# MosfetV4.net
KiCad netlist of a schematic drawn in EAGLE
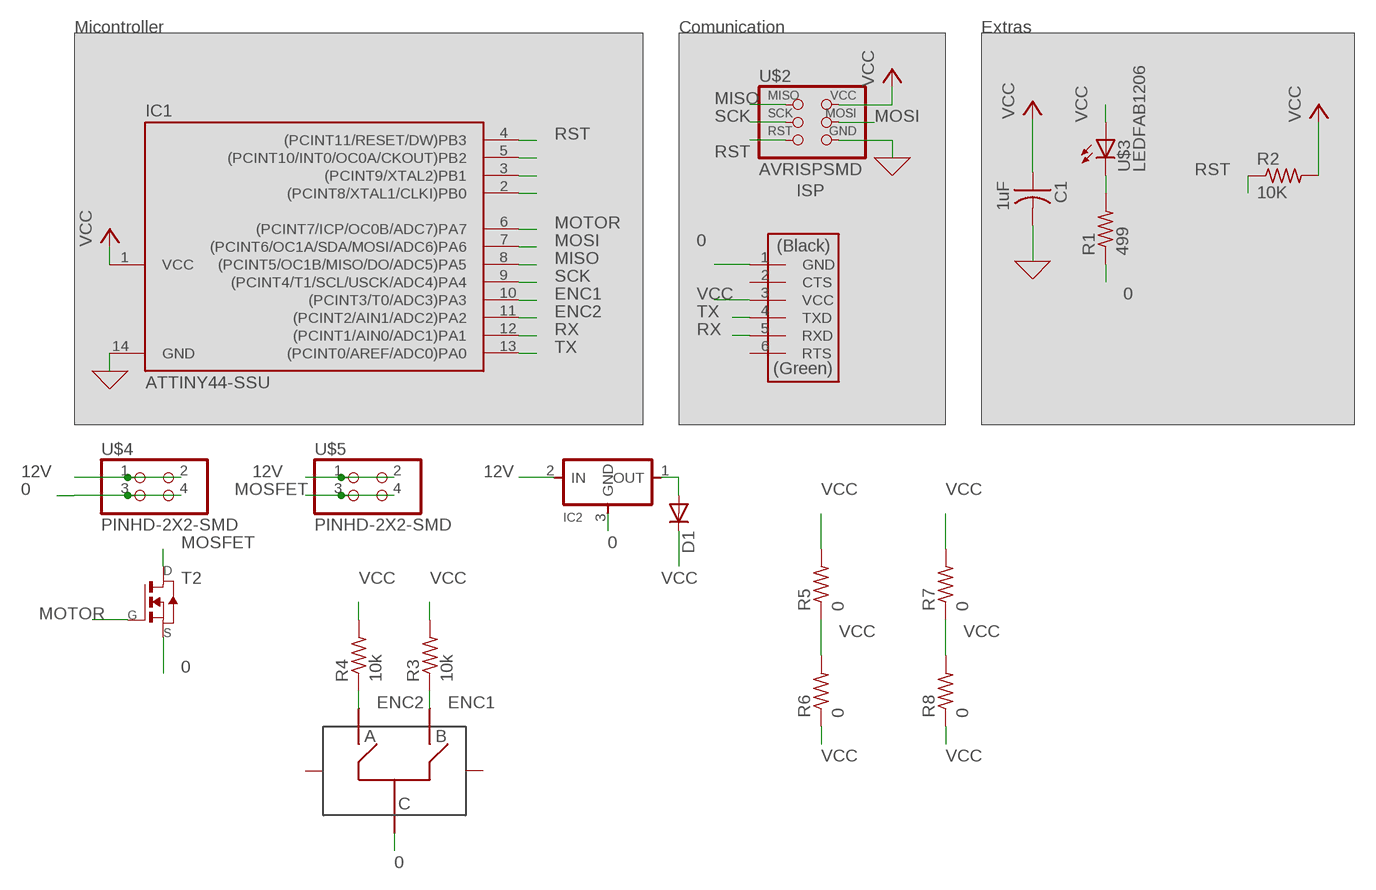
[diagram p0: schematic, sheet 1]

(export (version "E")
  (design (tool "Eeschema 10.0.6"))
  (components
    (comp (ref "C1")
      (value "1uF")
      (footprint "eagle-import:C1206FAB")
      (libsource (lib "eagle-import") (part "CAP-US1206FAB"))
    )
    (comp (ref "D1")
      (value "DIODESOD123")
      (footprint "eagle-import:SOD123")
      (libsource (lib "eagle-import") (part "DIODESOD123"))
    )
    (comp (ref "IC1")
      (value "ATTINY44-SSU")
      (footprint "eagle-import:SOIC14")
      (libsource (lib "eagle-import") (part "ATTINY44-SSU"))
    )
    (comp (ref "IC2")
      (value "REGULATORSOT23")
      (footprint "eagle-import:SOT23")
      (libsource (lib "eagle-import") (part "REGULATORSOT23"))
    )
    (comp (ref "R1")
      (value "499")
      (footprint "eagle-import:R1206FAB")
      (libsource (lib "eagle-import") (part "RES-US1206FAB"))
    )
    (comp (ref "R2")
      (value "10K")
      (footprint "eagle-import:R1206FAB")
      (libsource (lib "eagle-import") (part "RES-US1206FAB"))
    )
    (comp (ref "R3")
      (value "10k")
      (footprint "eagle-import:R1206FAB")
      (libsource (lib "eagle-import") (part "RES-US1206FAB"))
    )
    (comp (ref "R4")
      (value "10k")
      (footprint "eagle-import:R1206FAB")
      (libsource (lib "eagle-import") (part "RES-US1206FAB"))
    )
    (comp (ref "R5")
      (value "0")
      (footprint "eagle-import:R1206FAB")
      (libsource (lib "eagle-import") (part "RES-US1206FAB"))
    )
    (comp (ref "R6")
      (value "0")
      (footprint "eagle-import:R1206FAB")
      (libsource (lib "eagle-import") (part "RES-US1206FAB"))
    )
    (comp (ref "R7")
      (value "0")
      (footprint "eagle-import:R1206FAB")
      (libsource (lib "eagle-import") (part "RES-US1206FAB"))
    )
    (comp (ref "R8")
      (value "0")
      (footprint "eagle-import:R1206FAB")
      (libsource (lib "eagle-import") (part "RES-US1206FAB"))
    )
    (comp (ref "T2")
      (value "NMOSFETTO252")
      (footprint "eagle-import:TO252")
      (libsource (lib "eagle-import") (part "NMOSFETTO252"))
    )
    (comp (ref "U$1")
      (value "FTDI-SMD-HEADER")
      (footprint "eagle-import:1X06SMD")
      (libsource (lib "eagle-import") (part "FTDI-SMD-HEADER"))
    )
    (comp (ref "U$2")
      (value "AVRISPSMD")
      (footprint "eagle-import:2X03SMD")
      (libsource (lib "eagle-import") (part "AVRISPSMD"))
    )
    (comp (ref "U$3")
      (value "LEDFAB1206")
      (footprint "eagle-import:LED1206FAB")
      (libsource (lib "eagle-import") (part "LEDFAB1206"))
    )
    (comp (ref "U$4")
      (value "PINHD-2X2-SMD")
      (footprint "eagle-import:2X02SMD")
      (libsource (lib "eagle-import") (part "PINHD-2X2-SMD"))
    )
    (comp (ref "U$5")
      (value "PINHD-2X2-SMD")
      (footprint "eagle-import:2X02SMD")
      (libsource (lib "eagle-import") (part "PINHD-2X2-SMD"))
    )
    (comp (ref "U$6")
      (value "ALBS_ENCODER_STEC12E08")
      (footprint "eagle-import:STEC12E08")
      (libsource (lib "eagle-import") (part "ALBS_ENCODER_STEC12E08"))
    )
  )
  (nets
    (net (code "1") (name "/12V") (class "Default")
      (node (ref "IC2") (pin "2") (pinfunction "IN_2") (pintype "bidirectional"))
      (node (ref "U$4") (pin "1") (pinfunction "1_1") (pintype "passive"))
      (node (ref "U$4") (pin "2") (pinfunction "2_2") (pintype "passive"))
      (node (ref "U$5") (pin "1") (pinfunction "1_1") (pintype "passive"))
      (node (ref "U$5") (pin "2") (pinfunction "2_2") (pintype "passive"))
    )
    (net (code "2") (name "/ENC1") (class "Default")
      (node (ref "IC1") (pin "10") (pinfunction "(PCINT3/T0/ADC3)PA3_10") (pintype "bidirectional"))
      (node (ref "R3") (pin "1") (pinfunction "1_1") (pintype "passive"))
      (node (ref "U$6") (pin "P$B") (pinfunction "TERMINAL_B_P$B") (pintype "bidirectional"))
    )
    (net (code "3") (name "/ENC2") (class "Default")
      (node (ref "IC1") (pin "11") (pinfunction "(PCINT2/AIN1/ADC2)PA2_11") (pintype "bidirectional"))
      (node (ref "R4") (pin "1") (pinfunction "1_1") (pintype "passive"))
      (node (ref "U$6") (pin "P$A") (pinfunction "TERMINAL_A_P$A") (pintype "bidirectional"))
    )
    (net (code "4") (name "/MISO") (class "Default")
      (node (ref "IC1") (pin "8") (pinfunction "(PCINT5/OC1B/MISO/DO/ADC5)PA5_8") (pintype "bidirectional"))
      (node (ref "U$2") (pin "1") (pinfunction "MISO_1") (pintype "passive"))
    )
    (net (code "5") (name "/MOSFET") (class "Default")
      (node (ref "T2") (pin "3") (pinfunction "D_3") (pintype "passive"))
      (node (ref "U$5") (pin "3") (pinfunction "3_3") (pintype "passive"))
      (node (ref "U$5") (pin "4") (pinfunction "4_4") (pintype "passive"))
    )
    (net (code "6") (name "/MOSI") (class "Default")
      (node (ref "IC1") (pin "7") (pinfunction "(PCINT6/OC1A/SDA/MOSI/ADC6)PA6_7") (pintype "bidirectional"))
      (node (ref "U$2") (pin "4") (pinfunction "MOSI_4") (pintype "passive"))
    )
    (net (code "7") (name "/MOTOR") (class "Default")
      (node (ref "IC1") (pin "6") (pinfunction "(PCINT7/ICP/OC0B/ADC7)PA7_6") (pintype "bidirectional"))
      (node (ref "T2") (pin "1") (pinfunction "G_1") (pintype "passive"))
    )
    (net (code "8") (name "/RST") (class "Default")
      (node (ref "IC1") (pin "4") (pinfunction "(PCINT11/RESET/DW)PB3_4") (pintype "bidirectional"))
      (node (ref "R2") (pin "1") (pinfunction "1_1") (pintype "passive"))
      (node (ref "U$2") (pin "5") (pinfunction "RST_5") (pintype "passive"))
    )
    (net (code "9") (name "/RX") (class "Default")
      (node (ref "IC1") (pin "12") (pinfunction "(PCINT1/AIN0/ADC1)PA1_12") (pintype "bidirectional"))
      (node (ref "U$1") (pin "5") (pinfunction "RXD_5") (pintype "bidirectional"))
    )
    (net (code "10") (name "/SCK") (class "Default")
      (node (ref "IC1") (pin "9") (pinfunction "(PCINT4/T1/SCL/USCK/ADC4)PA4_9") (pintype "bidirectional"))
      (node (ref "U$2") (pin "3") (pinfunction "SCK_3") (pintype "passive"))
    )
    (net (code "11") (name "/TX") (class "Default")
      (node (ref "IC1") (pin "13") (pinfunction "(PCINT0/AREF/ADC0)PA0_13") (pintype "bidirectional"))
      (node (ref "U$1") (pin "4") (pinfunction "TXD_4") (pintype "bidirectional"))
    )
    (net (code "12") (name "GND") (class "Default")
      (node (ref "C1") (pin "2") (pinfunction "2_2") (pintype "passive"))
      (node (ref "IC1") (pin "14") (pinfunction "GND_14") (pintype "power_in"))
      (node (ref "IC2") (pin "3") (pinfunction "GND_3") (pintype "bidirectional"))
      (node (ref "R1") (pin "1") (pinfunction "1_1") (pintype "passive"))
      (node (ref "T2") (pin "2") (pinfunction "S_2") (pintype "passive"))
      (node (ref "U$1") (pin "1") (pinfunction "GND_1") (pintype "bidirectional"))
      (node (ref "U$2") (pin "6") (pinfunction "GND_6") (pintype "passive"))
      (node (ref "U$4") (pin "3") (pinfunction "3_3") (pintype "passive"))
      (node (ref "U$4") (pin "4") (pinfunction "4_4") (pintype "passive"))
      (node (ref "U$6") (pin "P$C") (pinfunction "TERMINAL_C_P$C") (pintype "bidirectional"))
    )
    (net (code "13") (name "Net-(D1-A)") (class "Default")
      (node (ref "D1") (pin "ANODE") (pinfunction "A_ANODE") (pintype "passive"))
      (node (ref "IC2") (pin "1") (pinfunction "OUT_1") (pintype "bidirectional"))
    )
    (net (code "14") (name "Net-(U$3-C)") (class "Default")
      (node (ref "R1") (pin "2") (pinfunction "2_2") (pintype "passive"))
      (node (ref "U$3") (pin "2") (pinfunction "C_2") (pintype "passive"))
    )
    (net (code "15") (name "VCC") (class "Default")
      (node (ref "C1") (pin "1") (pinfunction "1_1") (pintype "passive"))
      (node (ref "D1") (pin "CATHODE") (pinfunction "C_CATHODE") (pintype "passive"))
      (node (ref "IC1") (pin "1") (pinfunction "VCC_1") (pintype "power_in"))
      (node (ref "R2") (pin "2") (pinfunction "2_2") (pintype "passive"))
      (node (ref "R3") (pin "2") (pinfunction "2_2") (pintype "passive"))
      (node (ref "R4") (pin "2") (pinfunction "2_2") (pintype "passive"))
      (node (ref "R5") (pin "1") (pinfunction "1_1") (pintype "passive"))
      (node (ref "R5") (pin "2") (pinfunction "2_2") (pintype "passive"))
      (node (ref "R6") (pin "1") (pinfunction "1_1") (pintype "passive"))
      (node (ref "R6") (pin "2") (pinfunction "2_2") (pintype "passive"))
      (node (ref "R7") (pin "1") (pinfunction "1_1") (pintype "passive"))
      (node (ref "R7") (pin "2") (pinfunction "2_2") (pintype "passive"))
      (node (ref "R8") (pin "1") (pinfunction "1_1") (pintype "passive"))
      (node (ref "R8") (pin "2") (pinfunction "2_2") (pintype "passive"))
      (node (ref "U$1") (pin "3") (pinfunction "VCC_3") (pintype "bidirectional"))
      (node (ref "U$2") (pin "2") (pinfunction "VCC_2") (pintype "passive"))
      (node (ref "U$3") (pin "1") (pinfunction "A_1") (pintype "passive"))
    )
    (net (code "16") (name "unconnected-(IC1-(PCINT8{slash}XTAL1{slash}CLKI)PB0-Pad2)") (class "Default")
      (node (ref "IC1") (pin "2") (pinfunction "(PCINT8/XTAL1/CLKI)PB0_2") (pintype "bidirectional"))
    )
    (net (code "17") (name "unconnected-(IC1-(PCINT9{slash}XTAL2)PB1-Pad3)") (class "Default")
      (node (ref "IC1") (pin "3") (pinfunction "(PCINT9/XTAL2)PB1_3") (pintype "bidirectional"))
    )
    (net (code "18") (name "unconnected-(IC1-(PCINT10{slash}INT0{slash}OC0A{slash}CKOUT)PB2-Pad5)") (class "Default")
      (node (ref "IC1") (pin "5") (pinfunction "(PCINT10/INT0/OC0A/CKOUT)PB2_5") (pintype "bidirectional"))
    )
    (net (code "19") (name "unconnected-(U$1-CTS-Pad2)") (class "Default")
      (node (ref "U$1") (pin "2") (pinfunction "CTS_2") (pintype "bidirectional"))
    )
    (net (code "20") (name "unconnected-(U$1-RTS-Pad6)") (class "Default")
      (node (ref "U$1") (pin "6") (pinfunction "RTS_6") (pintype "bidirectional"))
    )
    (net (code "21") (name "unconnected-(U$6-PadP$CASE0)") (class "Default")
      (node (ref "U$6") (pin "P$CASE0") (pinfunction "P$CASE0_P$CASE0") (pintype "bidirectional"))
    )
    (net (code "22") (name "unconnected-(U$6-PadP$CASE1)") (class "Default")
      (node (ref "U$6") (pin "P$CASE1") (pinfunction "P$CASE1_P$CASE1") (pintype "bidirectional"))
    )
  )
)
